# MAGI_sPicoPower.net
KiCad netlist of a schematic drawn in Altium Designer
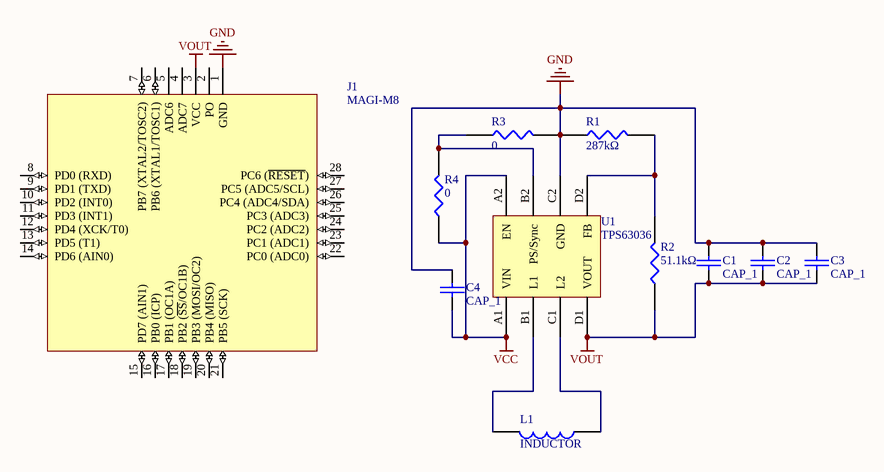
[diagram p0: MAGI'sPicoPower.SchDoc]

(export (version "E")
  (design (tool "Eeschema 10.0.6"))
  (components
    (comp (ref "C1")
      (value "CAP_1")
      (footprint "6-0805_L")
      (description "Capacitor")
      (libsource (lib "电容器") (part "CAP_1"))
    )
    (comp (ref "C2")
      (value "CAP_1")
      (footprint "6-0805_L")
      (description "Capacitor")
      (libsource (lib "电容器") (part "CAP_1"))
    )
    (comp (ref "C3")
      (value "CAP_1")
      (footprint "6-0805_L")
      (description "Capacitor")
      (libsource (lib "电容器") (part "CAP_1"))
    )
    (comp (ref "C4")
      (value "CAP_1")
      (footprint "6-0805_L")
      (description "Capacitor")
      (libsource (lib "电容器") (part "CAP_1"))
    )
    (comp (ref "J1") (value "MAGI-M8") (footprint "MAGI-M8") (libsource (lib "MAGI-M8") (part "MAGI-M8")))
    (comp (ref "L1") (value "INDUCTOR") (footprint "4*4") (libsource (lib "汇总") (part "INDUCTOR")))
    (comp (ref "R1") (value "287kΩ") (footprint "6-0805_L") (libsource (lib "电阻器") (part "RES1")))
    (comp (ref "R2") (value "51.1kΩ") (footprint "6-0805_L") (libsource (lib "电阻器") (part "RES1")))
    (comp (ref "R3") (value "0") (footprint "1608[0603]") (libsource (lib "电阻器") (part "RES1")))
    (comp (ref "R4") (value "0") (footprint "1608[0603]") (libsource (lib "电阻器") (part "RES1")))
    (comp (ref "U1") (value "TPS63036") (footprint "WCSP-8") (libsource (lib "PMIC") (part "TPS63036")))
  )
  (nets
    (net (code "1") (name "GND") (class "Default")
      (node (ref "C1") (pin "1") (pinfunction "1_1") (pintype "passive"))
      (node (ref "C2") (pin "1") (pinfunction "1_1") (pintype "passive"))
      (node (ref "C3") (pin "1") (pinfunction "1_1") (pintype "passive"))
      (node (ref "C4") (pin "1") (pinfunction "1_1") (pintype "passive"))
      (node (ref "J1") (pin "1") (pinfunction "GND_1") (pintype "power_in"))
      (node (ref "R1") (pin "1") (pinfunction "1_1") (pintype "passive"))
      (node (ref "R3") (pin "2") (pinfunction "2_2") (pintype "passive"))
      (node (ref "U1") (pin "C2") (pinfunction "GND_C2") (pintype "passive"))
    )
    (net (code "2") (name "Net-(U1-FB)") (class "Default")
      (node (ref "R1") (pin "2") (pinfunction "2_2") (pintype "passive"))
      (node (ref "R2") (pin "2") (pinfunction "2_2") (pintype "passive"))
      (node (ref "U1") (pin "D2") (pinfunction "FB_D2") (pintype "passive"))
    )
    (net (code "3") (name "Net-(U1-L1)") (class "Default")
      (node (ref "L1") (pin "2") (pinfunction "2_2") (pintype "passive"))
      (node (ref "U1") (pin "B1") (pinfunction "L1_B1") (pintype "passive"))
    )
    (net (code "4") (name "Net-(U1-L2)") (class "Default")
      (node (ref "L1") (pin "1") (pinfunction "1_1") (pintype "passive"))
      (node (ref "U1") (pin "C1") (pinfunction "L2_C1") (pintype "passive"))
    )
    (net (code "5") (name "Net-(U1-PS{slash}Sync)") (class "Default")
      (node (ref "R3") (pin "1") (pinfunction "1_1") (pintype "passive"))
      (node (ref "R4") (pin "2") (pinfunction "2_2") (pintype "passive"))
      (node (ref "U1") (pin "B2") (pinfunction "PS/Sync_B2") (pintype "passive"))
    )
    (net (code "6") (name "VCC") (class "Default")
      (node (ref "C4") (pin "2") (pinfunction "2_2") (pintype "passive"))
      (node (ref "R4") (pin "1") (pinfunction "1_1") (pintype "passive"))
      (node (ref "U1") (pin "A1") (pinfunction "VIN_A1") (pintype "passive"))
      (node (ref "U1") (pin "A2") (pinfunction "EN_A2") (pintype "passive"))
    )
    (net (code "7") (name "VOUT") (class "Default")
      (node (ref "C1") (pin "2") (pinfunction "2_2") (pintype "passive"))
      (node (ref "C2") (pin "2") (pinfunction "2_2") (pintype "passive"))
      (node (ref "C3") (pin "2") (pinfunction "2_2") (pintype "passive"))
      (node (ref "J1") (pin "3") (pinfunction "VCC_3") (pintype "power_in"))
      (node (ref "R2") (pin "1") (pinfunction "1_1") (pintype "passive"))
      (node (ref "U1") (pin "D1") (pinfunction "VOUT_D1") (pintype "passive"))
    )
    (net (code "8") (name "unconnected-(J1-ADC6-Pad5)") (class "Default")
      (node (ref "J1") (pin "5") (pinfunction "ADC6_5") (pintype "passive"))
    )
    (net (code "9") (name "unconnected-(J1-ADC7-Pad4)") (class "Default")
      (node (ref "J1") (pin "4") (pinfunction "ADC7_4") (pintype "passive"))
    )
    (net (code "10") (name "unconnected-(J1-PB0_(ICP)-Pad16)") (class "Default")
      (node (ref "J1") (pin "16") (pinfunction "PB0_(ICP)_16") (pintype "bidirectional"))
    )
    (net (code "11") (name "unconnected-(J1-PB1_(OC1A)-Pad17)") (class "Default")
      (node (ref "J1") (pin "17") (pinfunction "PB1_(OC1A)_17") (pintype "bidirectional"))
    )
    (net (code "12") (name "unconnected-(J1-PB2_(~{SS}{slash}OC1B)-Pad18)") (class "Default")
      (node (ref "J1") (pin "18") (pinfunction "PB2_(~{SS}/OC1B)_18") (pintype "bidirectional"))
    )
    (net (code "13") (name "unconnected-(J1-PB3_(MOSI{slash}OC2)-Pad19)") (class "Default")
      (node (ref "J1") (pin "19") (pinfunction "PB3_(MOSI/OC2)_19") (pintype "bidirectional"))
    )
    (net (code "14") (name "unconnected-(J1-PB4_(MISO)-Pad20)") (class "Default")
      (node (ref "J1") (pin "20") (pinfunction "PB4_(MISO)_20") (pintype "bidirectional"))
    )
    (net (code "15") (name "unconnected-(J1-PB5_(SCK)-Pad21)") (class "Default")
      (node (ref "J1") (pin "21") (pinfunction "PB5_(SCK)_21") (pintype "bidirectional"))
    )
    (net (code "16") (name "unconnected-(J1-PB6_(XTAL1{slash}TOSC1)-Pad6)") (class "Default")
      (node (ref "J1") (pin "6") (pinfunction "PB6_(XTAL1/TOSC1)_6") (pintype "bidirectional"))
    )
    (net (code "17") (name "unconnected-(J1-PB7_(XTAL2{slash}TOSC2)-Pad7)") (class "Default")
      (node (ref "J1") (pin "7") (pinfunction "PB7_(XTAL2/TOSC2)_7") (pintype "bidirectional"))
    )
    (net (code "18") (name "unconnected-(J1-PC0_(ADC0)-Pad22)") (class "Default")
      (node (ref "J1") (pin "22") (pinfunction "PC0_(ADC0)_22") (pintype "bidirectional"))
    )
    (net (code "19") (name "unconnected-(J1-PC1_(ADC1)-Pad23)") (class "Default")
      (node (ref "J1") (pin "23") (pinfunction "PC1_(ADC1)_23") (pintype "bidirectional"))
    )
    (net (code "20") (name "unconnected-(J1-PC2_(ADC2)-Pad24)") (class "Default")
      (node (ref "J1") (pin "24") (pinfunction "PC2_(ADC2)_24") (pintype "bidirectional"))
    )
    (net (code "21") (name "unconnected-(J1-PC3_(ADC3)-Pad25)") (class "Default")
      (node (ref "J1") (pin "25") (pinfunction "PC3_(ADC3)_25") (pintype "bidirectional"))
    )
    (net (code "22") (name "unconnected-(J1-PC4_(ADC4{slash}SDA)-Pad26)") (class "Default")
      (node (ref "J1") (pin "26") (pinfunction "PC4_(ADC4/SDA)_26") (pintype "bidirectional"))
    )
    (net (code "23") (name "unconnected-(J1-PC5_(ADC5{slash}SCL)-Pad27)") (class "Default")
      (node (ref "J1") (pin "27") (pinfunction "PC5_(ADC5/SCL)_27") (pintype "bidirectional"))
    )
    (net (code "24") (name "unconnected-(J1-PC6_(~{RESET})-Pad28)") (class "Default")
      (node (ref "J1") (pin "28") (pinfunction "PC6_(~{RESET})_28") (pintype "bidirectional"))
    )
    (net (code "25") (name "unconnected-(J1-PD0_(RXD)-Pad8)") (class "Default")
      (node (ref "J1") (pin "8") (pinfunction "PD0_(RXD)_8") (pintype "bidirectional"))
    )
    (net (code "26") (name "unconnected-(J1-PD1_(TXD)-Pad9)") (class "Default")
      (node (ref "J1") (pin "9") (pinfunction "PD1_(TXD)_9") (pintype "bidirectional"))
    )
    (net (code "27") (name "unconnected-(J1-PD2_(INT0)-Pad10)") (class "Default")
      (node (ref "J1") (pin "10") (pinfunction "PD2_(INT0)_10") (pintype "bidirectional"))
    )
    (net (code "28") (name "unconnected-(J1-PD3_(INT1)-Pad11)") (class "Default")
      (node (ref "J1") (pin "11") (pinfunction "PD3_(INT1)_11") (pintype "bidirectional"))
    )
    (net (code "29") (name "unconnected-(J1-PD4_(XCK{slash}T0)-Pad12)") (class "Default")
      (node (ref "J1") (pin "12") (pinfunction "PD4_(XCK/T0)_12") (pintype "bidirectional"))
    )
    (net (code "30") (name "unconnected-(J1-PD5_(T1)-Pad13)") (class "Default")
      (node (ref "J1") (pin "13") (pinfunction "PD5_(T1)_13") (pintype "bidirectional"))
    )
    (net (code "31") (name "unconnected-(J1-PD6_(AIN0)-Pad14)") (class "Default")
      (node (ref "J1") (pin "14") (pinfunction "PD6_(AIN0)_14") (pintype "bidirectional"))
    )
    (net (code "32") (name "unconnected-(J1-PD7_(AIN1)-Pad15)") (class "Default")
      (node (ref "J1") (pin "15") (pinfunction "PD7_(AIN1)_15") (pintype "bidirectional"))
    )
    (net (code "33") (name "unconnected-(J1-PO-Pad2)") (class "Default")
      (node (ref "J1") (pin "2") (pinfunction "PO_2") (pintype "power_in"))
    )
  )
)
